# Fonteslineares.net
KiCad netlist of a schematic drawn in Altium Designer
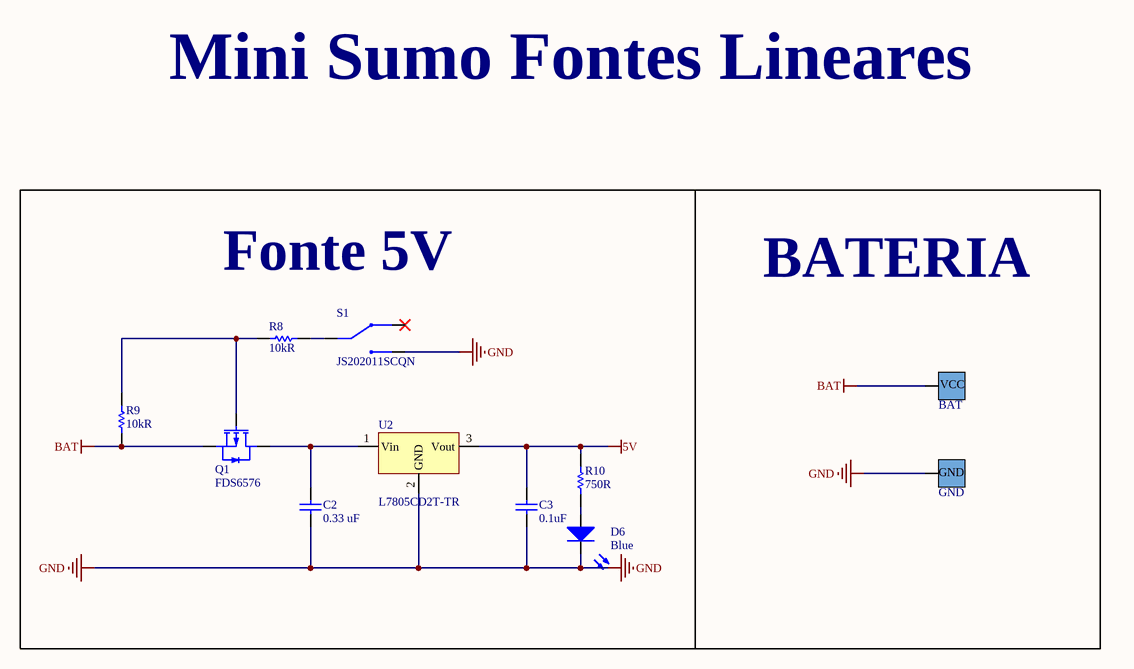
[diagram p0: Fonteslineares.SchDoc]

(export (version "E")
  (design (tool "Eeschema 10.0.6"))
  (components
    (comp (ref "BAT")
      (value "Source Pad")
      (footprint "PAD_ALIMENTAÇÃO_MINI")
      (description "VCC PAD MINI SUMÔ")
      (libsource (lib "Uai!Tecas") (part "Source Pad Mini Sumô"))
    )
    (comp (ref "C2")
      (value "0.33 uF")
      (footprint "C0805")
      (description "CAP CER 0.33UF 25V X7R 0805")
      (fields
        (field (name "MANUFACTURER") "Murata Eletronics")
        (field (name "PART NUMBER") "GCM21BR71E334KA37K")
        (field (name "LIBRARY CONTROL - PERSON THAT CHECKED FOOTPRINT") "Nikaum")
        (field (name "LIBRARY CONTROL - PERSON THAT CHECKED SCHEMATIC") "Nikaum")
        (field (name "LIBRARY CONTROL - PERSON THAT DID THE LAST UPDATE FOOTPRINT") "Nikaum")
        (field (name "LIBRARY CONTROL - PERSON THAT DID THE LAST UPDATE SCHEMATIC") "Nikaum")
      )
      (libsource (lib "Uai!Tecas") (part "GCM21BR71E334KA37K"))
    )
    (comp (ref "C3")
      (value "0.1uF")
      (footprint "C0805")
      (description "CAP CER 0.1uF 25V X7R 0805")
      (fields
        (field (name "MANUFACTURER") "Kemet")
        (field (name "PART NUMBER") "C0805C104M3RACTU")
        (field (name "LIBRARY CONTROL - PERSON THAT CHECKED SCHEMATIC") "Guilherme")
        (field (name "LIBRARY CONTROL - PERSON THAT DID THE LAST UPDATE SCHEMATIC") "Marcos")
      )
      (libsource (lib "Uai!Tecas") (part "C0805C104M3RACTU"))
    )
    (comp (ref "D6")
      (value "Blue")
      (footprint "DIODO_2-SMD-3215")
      (description "LED 75mW BLUE 45MCD 3215")
      (fields
        (field (name "MANUFACTURER") "Everlight Electronics")
        (field (name "PART NUMBER") "EAST3215BA5")
        (field (name "LIBRARY CONTROL - PERSON THAT CHECKED FOOTPRINT") "Lucas")
        (field (name "LIBRARY CONTROL - PERSON THAT CHECKED SCHEMATIC") "Lucas")
        (field (name "LIBRARY CONTROL - PERSON THAT DID THE LAST UPDATE FOOTPRINT") "Stéfany (Ster)")
        (field (name "LIBRARY CONTROL - PERSON THAT DID THE LAST UPDATE SCHEMATIC") "Stéfany (Ster)")
      )
      (libsource (lib "Diodo") (part "EAST3215BA5"))
    )
    (comp (ref "GND")
      (value "Ground Pad")
      (footprint "PAD_ALIMENTAÇÃO_MINI")
      (description "GND PAD MINI SUMÔ")
      (libsource (lib "Uai!Tecas") (part "Ground Pad Mini Sumô"))
    )
    (comp (ref "Q1")
      (value "FDS6576")
      (footprint "SOIC-8")
      (description "MOSFET P-CH 20V 11A SOIC-8")
      (fields (field (name "PART NUMBER") "SOIC-8") (field (name "MANUFACTURER") "onsemi / Fairchild"))
      (libsource (lib "Uai!Tecas") (part "FDS6576"))
    )
    (comp (ref "R8")
      (value "10kR")
      (footprint "RESISTOR_0603")
      (description "RES SMD 10K OHM 5% 1/10W 0603")
      (fields
        (field (name "MANUFACTURER") "Yageo")
        (field (name "PART NUMBER") "RC0603JR-0710KL")
        (field (name "LIBRARY CONTROL - PERSON THAT CHECKED SCHEMATIC") "Marcos")
        (field (name "LIBRARY CONTROL - PERSON THAT DID THE LAST UPDATE FOOTPRINT") "Dalarme")
        (field (name "LIBRARY CONTROL - PERSON THAT DID THE LAST UPDATE SCHEMATIC") "Marcos")
      )
      (libsource (lib "Uai!Tecas") (part "RC0603JR-0710KL"))
    )
    (comp (ref "R9")
      (value "10kR")
      (footprint "RESISTOR_0603")
      (description "RES SMD 10K OHM 5% 1/10W 0603")
      (fields
        (field (name "MANUFACTURER") "Yageo")
        (field (name "PART NUMBER") "RC0603JR-0710KL")
        (field (name "LIBRARY CONTROL - PERSON THAT CHECKED SCHEMATIC") "Marcos")
        (field (name "LIBRARY CONTROL - PERSON THAT DID THE LAST UPDATE FOOTPRINT") "Dalarme")
        (field (name "LIBRARY CONTROL - PERSON THAT DID THE LAST UPDATE SCHEMATIC") "Marcos")
      )
      (libsource (lib "Uai!Tecas") (part "RC0603JR-0710KL"))
    )
    (comp (ref "R10")
      (value "750R")
      (footprint "RESISTOR_0805")
      (description "RES SMD 750 OHM 5% 1/8W 0805")
      (fields
        (field (name "MANUFACTURER") "Panasonic")
        (field (name "PART NUMBER") "ERJ-6GEYJ751V")
        (field (name "LIBRARY CONTROL - PERSON THAT CHECKED FOOTPRINT") "Nikaum")
        (field (name "LIBRARY CONTROL - PERSON THAT CHECKED SCHEMATIC") "Guilherme")
        (field (name "LIBRARY CONTROL - PERSON THAT DID THE LAST UPDATE FOOTPRINT") "Dalarme")
        (field (name "LIBRARY CONTROL - PERSON THAT DID THE LAST UPDATE SCHEMATIC") "Nikaum")
      )
      (libsource (lib "Uai!Tecas") (part "ERJ-6GEYJ751V"))
    )
    (comp (ref "S1")
      (value "JS202011SCQN")
      (footprint "DPDT")
      (description "DEEP SWITCH 4 POSITIONS")
      (fields
        (field (name "MANUFACTURER") "C&K")
        (field (name "MOUSER PART NUMBER") "611-JS202011SCQN")
        (field (name "LIBRARY CONTROL - PERSON THAT CHECKED FOOTPRINT") "Nikaum")
        (field (name "LIBRARY CONTROL - PERSON THAT CHECKED SCHEMATIC") "Nikaum")
        (field (name "LIBRARY CONTROL - PERSON THAT DID THE LAST UPDATE FOOTPRINT") "Nikaum")
        (field (name "LIBRARY CONTROL - PERSON THAT DID THE LAST UPDATE SCHEMATIC") "Nikaum")
      )
      (libsource (lib "Uai!Tecas") (part "JS202011SCQN"))
    )
    (comp (ref "U2")
      (value "L7805CD2T-TR")
      (footprint "D2PAK")
      (description "IC REG LINEAR 5V 1A D2PAK")
      (fields
        (field (name "MANUFACTURER") "ST")
        (field (name "LIBRARY CONTROL - PERSON THAT CHECKED FOOTPRINT") "Nícolas")
        (field (name "LIBRARY CONTROL - PERSON THAT CHECKED SCHEMATIC") "Nícolas")
        (field (name "LIBRARY CONTROL - PERSON THAT DID THE LAST UPDATE SCHEMATIC") "Nícolas")
      )
      (libsource (lib "Uai!Tecas") (part "L7805CD2T-TR"))
    )
  )
  (nets
    (net (code "1") (name "5V") (class "Default")
      (node (ref "C3") (pin "2") (pinfunction "2_2") (pintype "passive"))
      (node (ref "R10") (pin "2") (pinfunction "2_2") (pintype "passive"))
      (node (ref "U2") (pin "3") (pinfunction "Vout_3") (pintype "power_in"))
    )
    (net (code "2") (name "BAT") (class "Default")
      (node (ref "BAT") (pin "A") (pinfunction "VCC_A") (pintype "passive"))
      (node (ref "Q1") (pin "S") (pinfunction "S_S") (pintype "passive"))
      (node (ref "R9") (pin "1") (pinfunction "1_1") (pintype "passive"))
    )
    (net (code "3") (name "GND") (class "Default")
      (node (ref "C2") (pin "1") (pinfunction "1_1") (pintype "passive"))
      (node (ref "C3") (pin "1") (pinfunction "1_1") (pintype "passive"))
      (node (ref "D6") (pin "C") (pinfunction "C_C") (pintype "passive"))
      (node (ref "GND") (pin "A") (pinfunction "GND_A") (pintype "passive"))
      (node (ref "S1") (pin "A3") (pinfunction "3_A3") (pintype "passive"))
      (node (ref "U2") (pin "2") (pinfunction "GND_2") (pintype "power_in"))
    )
    (net (code "4") (name "Net-(D6-PadA)") (class "Default")
      (node (ref "D6") (pin "A") (pinfunction "A_A") (pintype "passive"))
      (node (ref "R10") (pin "1") (pinfunction "1_1") (pintype "passive"))
    )
    (net (code "5") (name "Net-(Q1-PadG)") (class "Default")
      (node (ref "Q1") (pin "G") (pinfunction "G_G") (pintype "passive"))
      (node (ref "R8") (pin "2") (pinfunction "2_2") (pintype "passive"))
      (node (ref "R9") (pin "2") (pinfunction "2_2") (pintype "passive"))
    )
    (net (code "6") (name "Net-(S1-1)") (class "Default")
      (node (ref "R8") (pin "1") (pinfunction "1_1") (pintype "passive"))
      (node (ref "S1") (pin "A1") (pinfunction "1_A1") (pintype "passive"))
    )
    (net (code "7") (name "Net-(U2-Vin)") (class "Default")
      (node (ref "C2") (pin "2") (pinfunction "2_2") (pintype "passive"))
      (node (ref "Q1") (pin "D") (pinfunction "D_D") (pintype "passive"))
      (node (ref "U2") (pin "1") (pinfunction "Vin_1") (pintype "power_in"))
    )
    (net (code "8") (name "unconnected-(S1-4-PadA2)") (class "Default")
      (node (ref "S1") (pin "A2") (pinfunction "4_A2") (pintype "passive+no_connect"))
    )
  )
)
